# Vapeix_mini_Shield.net
KiCad netlist of a schematic drawn in Altium Designer
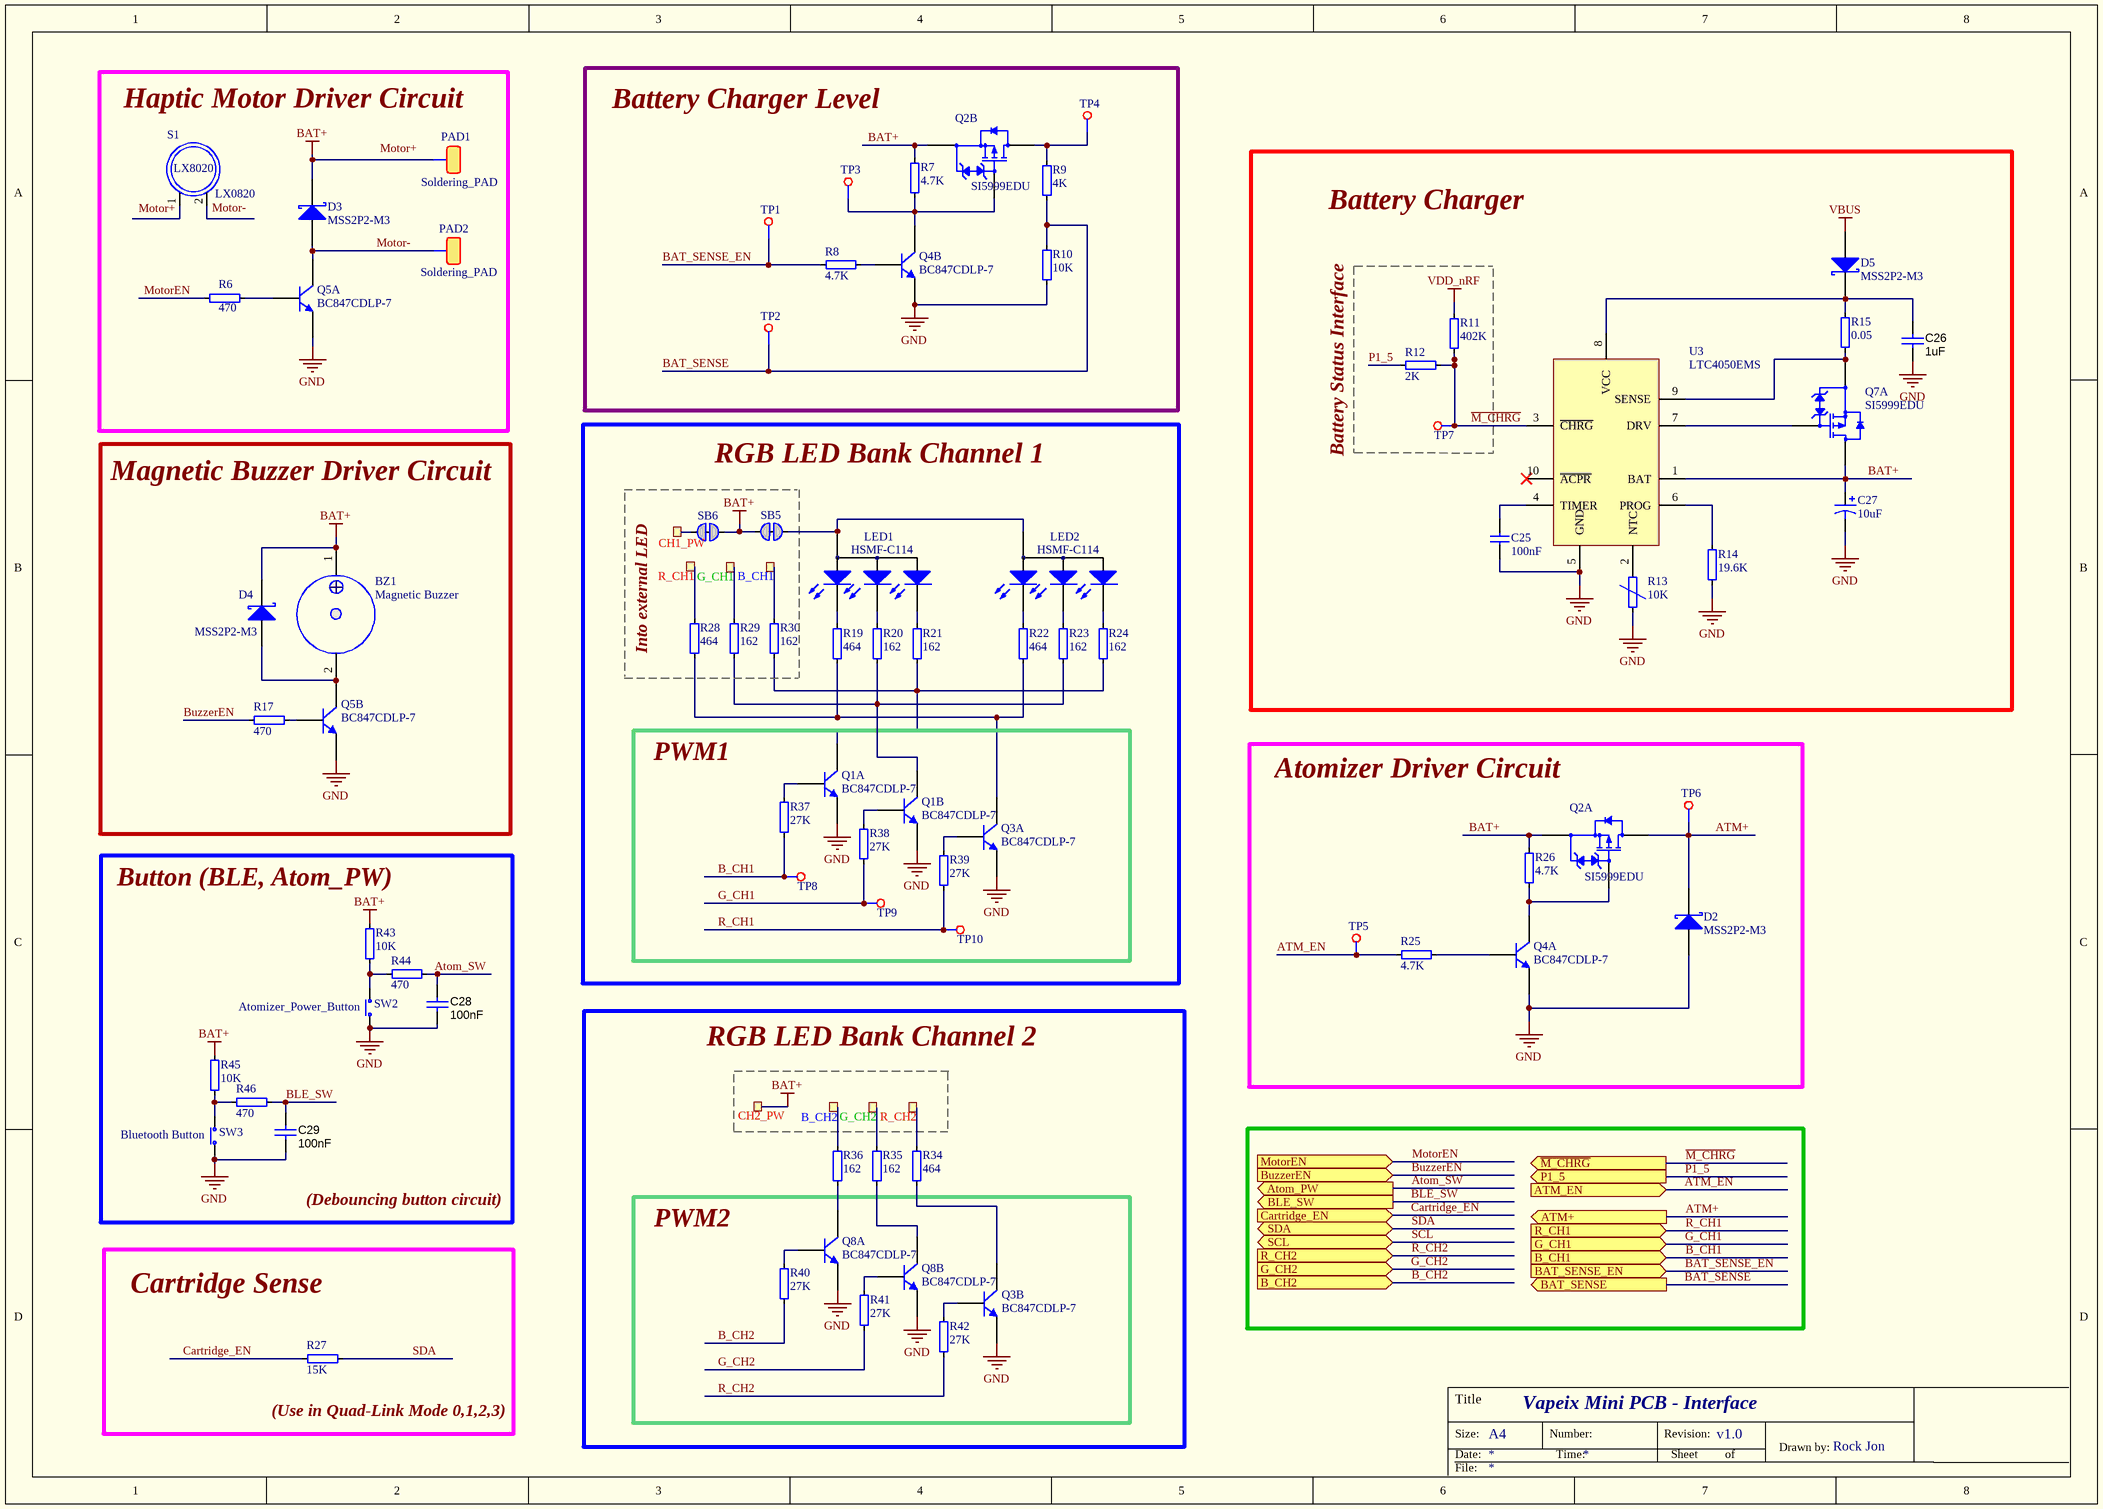
[diagram p0: Vapeix_mini_Shield.SchDoc]

(export (version "E")
  (design (tool "Eeschema 10.0.6"))
  (components
    (comp (ref "BZ1")
      (value "Magnetic Buzzer")
      (footprint "Magnetic Buzzer")
      (libsource (lib "VapeixS_LIB") (part "Magnetic Buzzer"))
    )
    (comp (ref "B_CH1")
      (value "TP")
      (footprint "TESTPAD-TH")
      (description "Testpoint, through hole")
      (fields (field (name "PART NUMBER") "Testpoint TH") (field (name "PUBLISHER") "Nordic Semiconductor"))
      (libsource (lib "pca10040") (part "TESTPAD_TH"))
    )
    (comp (ref "B_CH2")
      (value "TP")
      (footprint "TESTPAD-TH")
      (description "Testpoint, through hole")
      (fields (field (name "PART NUMBER") "Testpoint TH") (field (name "PUBLISHER") "Nordic Semiconductor"))
      (libsource (lib "pca10040") (part "TESTPAD_TH"))
    )
    (comp (ref "C25")
      (value "100nF")
      (footprint "C0201")
      (description "Capacitor, X7R, ±10%")
      (fields (field (name "PART NUMBER") "C0402-100n") (field (name "PUBLISHER") "Nordic Semiconductor"))
      (libsource (lib "Nordic Passive DB") (part "CAP"))
    )
    (comp (ref "C26")
      (value "~")
      (footprint "C0201")
      (description "CAP, CERM, 10 µF, 10 V, +/- 10%, X5R, 0805")
      (fields
        (field (name "PARTNUMBER") "GRM219R61A106KE44D")
        (field (name "VALUEDISPLAYED") "1uF")
        (field (name "MANUFACTURER") "MuRata")
        (field (name "PUBLISHER") "Texas Instruments")
      )
      (libsource (lib "Capacitor_Ceramic") (part "GRM219R61A106KE44D"))
    )
    (comp (ref "C27")
      (value "10uF")
      (footprint "CAPC1005X04L")
      (description "Polarized Capacitor (Surface Mount)")
      (fields (field (name "Comment") "Cap Pol3") (field (name "PUBLISHER") "Altium Limited"))
      (libsource (lib "Miscellaneous Devices") (part "Cap Pol3"))
    )
    (comp (ref "C28")
      (value "~")
      (footprint "C0201")
      (description "CAP, CERM, 10 µF, 10 V, +/- 10%, X5R, 0805")
      (fields
        (field (name "PARTNUMBER") "GRM219R61A106KE44D")
        (field (name "VALUEDISPLAYED") "100nF")
        (field (name "MANUFACTURER") "MuRata")
        (field (name "PUBLISHER") "Texas Instruments")
      )
      (libsource (lib "Capacitor_Ceramic") (part "GRM219R61A106KE44D"))
    )
    (comp (ref "C29")
      (value "~")
      (footprint "C0201")
      (description "CAP, CERM, 10 µF, 10 V, +/- 10%, X5R, 0805")
      (fields
        (field (name "PARTNUMBER") "GRM219R61A106KE44D")
        (field (name "VALUEDISPLAYED") "100nF")
        (field (name "MANUFACTURER") "MuRata")
        (field (name "PUBLISHER") "Texas Instruments")
      )
      (libsource (lib "Capacitor_Ceramic") (part "GRM219R61A106KE44D"))
    )
    (comp (ref "CH1_PW")
      (value "TP")
      (footprint "TESTPAD-TH")
      (description "Testpoint, through hole")
      (fields (field (name "PART NUMBER") "Testpoint TH") (field (name "PUBLISHER") "Nordic Semiconductor"))
      (libsource (lib "pca10040") (part "TESTPAD_TH"))
    )
    (comp (ref "CH2_PW")
      (value "TP")
      (footprint "TESTPAD-TH")
      (description "Testpoint, through hole")
      (fields (field (name "PART NUMBER") "Testpoint TH") (field (name "PUBLISHER") "Nordic Semiconductor"))
      (libsource (lib "pca10040") (part "TESTPAD_TH"))
    )
    (comp (ref "D2")
      (value "MSS2P2-M3")
      (footprint "MSS2P2-M3")
      (description "DIODE SCHOTTKY 20V 2A MICROSMP")
      (fields
        (field (name "MANUFACTURER") "Vishay Semiconductor Diodes Division")
        (field (name "MANUFACTURER PART NUMBER") "MSS2P2-M3/89A")
      )
      (libsource (lib "VapeixS_LIB") (part "MSS2P2-M3/89A"))
    )
    (comp (ref "D3")
      (value "MSS2P2-M3")
      (footprint "MSS2P2-M3")
      (description "DIODE SCHOTTKY 20V 2A MICROSMP")
      (fields
        (field (name "MANUFACTURER") "Vishay Semiconductor Diodes Division")
        (field (name "MANUFACTURER PART NUMBER") "MSS2P2-M3/89A")
      )
      (libsource (lib "VapeixS_LIB") (part "MSS2P2-M3/89A"))
    )
    (comp (ref "D4")
      (value "MSS2P2-M3")
      (footprint "MSS2P2-M3")
      (description "DIODE SCHOTTKY 20V 2A MICROSMP")
      (fields
        (field (name "MANUFACTURER") "Vishay Semiconductor Diodes Division")
        (field (name "MANUFACTURER PART NUMBER") "MSS2P2-M3/89A")
      )
      (libsource (lib "VapeixS_LIB") (part "MSS2P2-M3/89A"))
    )
    (comp (ref "D5")
      (value "MSS2P2-M3")
      (footprint "MSS2P2-M3")
      (description "DIODE SCHOTTKY 20V 2A MICROSMP")
      (fields
        (field (name "MANUFACTURER") "Vishay Semiconductor Diodes Division")
        (field (name "MANUFACTURER PART NUMBER") "MSS2P2-M3/89A")
      )
      (libsource (lib "VapeixS_LIB") (part "MSS2P2-M3/89A"))
    )
    (comp (ref "G_CH1")
      (value "TP")
      (footprint "TESTPAD-TH")
      (description "Testpoint, through hole")
      (fields (field (name "PART NUMBER") "Testpoint TH") (field (name "PUBLISHER") "Nordic Semiconductor"))
      (libsource (lib "pca10040") (part "TESTPAD_TH"))
    )
    (comp (ref "G_CH2")
      (value "TP")
      (footprint "TESTPAD-TH")
      (description "Testpoint, through hole")
      (fields (field (name "PART NUMBER") "Testpoint TH") (field (name "PUBLISHER") "Nordic Semiconductor"))
      (libsource (lib "pca10040") (part "TESTPAD_TH"))
    )
    (comp (ref "LED1")
      (value "HSMF-C114")
      (footprint "HSMF-C114")
      (description "LED RGB DIFFUSED 0606 SMD")
      (fields (field (name "MANUFACTURER") "Broadcom Limited"))
      (libsource (lib "VapeixS_LIB") (part "HSMF-C114"))
    )
    (comp (ref "LED2")
      (value "HSMF-C114")
      (footprint "HSMF-C114")
      (description "LED RGB DIFFUSED 0606 SMD")
      (fields (field (name "MANUFACTURER") "Broadcom Limited"))
      (libsource (lib "VapeixS_LIB") (part "HSMF-C114"))
    )
    (comp (ref "PAD1")
      (value "Soldering_PAD")
      (footprint "Soldering_PAD")
      (description "Soldering PAD")
      (libsource (lib "VapeixS_LIB") (part "Soldering_PAD"))
    )
    (comp (ref "PAD2")
      (value "Soldering_PAD")
      (footprint "Soldering_PAD")
      (description "Soldering PAD")
      (libsource (lib "VapeixS_LIB") (part "Soldering_PAD"))
    )
    (comp (ref "Q1")
      (value "BC847CDLP-7")
      (footprint "BC847CDLP-7")
      (description "TRANS 2NPN 45V 0.1A 6DFN")
      (fields (field (name "MANUFACTURER") "Diodes Incorporated"))
      (libsource (lib "") (part "BC847CDLP-7_1"))
    )
    (comp (ref "Q2")
      (value "SI5999EDU")
      (footprint "SI5999EDU")
      (description "MOSFET 2P-CH 20V 6A POWERPAK")
      (fields
        (field (name "MANUFACTURER") "Vishay Siliconix")
        (field (name "MANUFACTURER PART NUMBER") "SI5999EDU-T1-GE3")
      )
      (libsource (lib "") (part "SI5999EDU-T1-GE3_2"))
    )
    (comp (ref "Q3")
      (value "BC847CDLP-7")
      (footprint "BC847CDLP-7")
      (description "TRANS 2NPN 45V 0.1A 6DFN")
      (fields (field (name "MANUFACTURER") "Diodes Incorporated"))
      (libsource (lib "VapeixS_LIB") (part "BC847CDLP-7"))
    )
    (comp (ref "Q4")
      (value "BC847CDLP-7")
      (footprint "BC847CDLP-7")
      (description "TRANS 2NPN 45V 0.1A 6DFN")
      (fields (field (name "MANUFACTURER") "Diodes Incorporated"))
      (libsource (lib "") (part "BC847CDLP-7_3"))
    )
    (comp (ref "Q5")
      (value "BC847CDLP-7")
      (footprint "BC847CDLP-7")
      (description "TRANS 2NPN 45V 0.1A 6DFN")
      (fields (field (name "MANUFACTURER") "Diodes Incorporated"))
      (libsource (lib "") (part "BC847CDLP-7_1"))
    )
    (comp (ref "Q7")
      (value "SI5999EDU")
      (footprint "SI5999EDU")
      (description "MOSFET 2P-CH 20V 6A POWERPAK")
      (fields
        (field (name "MANUFACTURER") "Vishay Siliconix")
        (field (name "MANUFACTURER PART NUMBER") "SI5999EDU-T1-GE3")
      )
      (libsource (lib "VapeixS_LIB") (part "SI5999EDU-T1-GE3"))
    )
    (comp (ref "Q8")
      (value "BC847CDLP-7")
      (footprint "BC847CDLP-7")
      (description "TRANS 2NPN 45V 0.1A 6DFN")
      (fields (field (name "MANUFACTURER") "Diodes Incorporated"))
      (libsource (lib "VapeixS_LIB") (part "BC847CDLP-7"))
    )
    (comp (ref "R6")
      (value "470")
      (footprint "R0201")
      (description "Resistor, ±1%, 0.063W")
      (fields (field (name "PART NUMBER") "R0402-10k") (field (name "PUBLISHER") "Nordic Semiconductor"))
      (libsource (lib "Nordic Passive DB") (part "RES_1"))
    )
    (comp (ref "R7")
      (value "4.7K")
      (footprint "R0201")
      (description "Resistor, ±1%, 0.063W")
      (fields (field (name "PART NUMBER") "R0402-10k") (field (name "PUBLISHER") "Nordic Semiconductor"))
      (libsource (lib "Nordic Passive DB") (part "RES_1"))
    )
    (comp (ref "R8")
      (value "4.7K")
      (footprint "R0201")
      (description "Resistor, ±1%, 0.063W")
      (fields (field (name "PART NUMBER") "R0402-10k") (field (name "PUBLISHER") "Nordic Semiconductor"))
      (libsource (lib "Nordic Passive DB") (part "RES_1"))
    )
    (comp (ref "R9")
      (value "4K")
      (footprint "R0201")
      (description "Resistor, ±1%, 0.063W")
      (fields (field (name "PART NUMBER") "R0402-10k") (field (name "PUBLISHER") "Nordic Semiconductor"))
      (libsource (lib "Nordic Passive DB") (part "RES_1"))
    )
    (comp (ref "R10")
      (value "10K")
      (footprint "R0201")
      (description "Resistor, ±1%, 0.063W")
      (fields (field (name "PART NUMBER") "R0402-10k") (field (name "PUBLISHER") "Nordic Semiconductor"))
      (libsource (lib "Nordic Passive DB") (part "RES_1"))
    )
    (comp (ref "R11")
      (value "402K")
      (footprint "R0201")
      (description "Resistor, ±1%, 0.063W")
      (fields (field (name "PART NUMBER") "R0402-10k") (field (name "PUBLISHER") "Nordic Semiconductor"))
      (libsource (lib "Nordic Passive DB") (part "RES_1"))
    )
    (comp (ref "R12")
      (value "2K")
      (footprint "R0201")
      (description "Resistor, ±1%, 0.063W")
      (fields (field (name "PART NUMBER") "R0402-10k") (field (name "PUBLISHER") "Nordic Semiconductor"))
      (libsource (lib "Nordic Passive DB") (part "RES_1"))
    )
    (comp (ref "R13")
      (value "10K")
      (footprint "RL0503-5820-97-MS")
      (description "THERMISTOR MINI-SENS NTC 10K OHM")
      (fields
        (field (name "MANUFACTURER") "Amphenol Advanced Sensors")
        (field (name "MANUFACTURER PART NUMBER") "RL0503-5820-97-MS")
      )
      (libsource (lib "VapeixS_LIB") (part "RL0503-5820-97-MS"))
    )
    (comp (ref "R14")
      (value "19.6K")
      (footprint "R0201")
      (description "Resistor, ±1%, 0.063W")
      (fields (field (name "PART NUMBER") "R0402-10k") (field (name "PUBLISHER") "Nordic Semiconductor"))
      (libsource (lib "Nordic Passive DB") (part "RES_1"))
    )
    (comp (ref "R15")
      (value "0.05")
      (footprint "R0402")
      (description "Resistor, ±1%, 0.063W")
      (fields (field (name "PART NUMBER") "R0402-10k") (field (name "PUBLISHER") "Nordic Semiconductor"))
      (libsource (lib "Nordic Passive DB") (part "RES_1"))
    )
    (comp (ref "R17")
      (value "470")
      (footprint "RESC1005X04L")
      (description "Resistor, ±1%, 0.063W")
      (fields (field (name "PART NUMBER") "R0402-10k") (field (name "PUBLISHER") "Nordic Semiconductor"))
      (libsource (lib "Nordic Passive DB") (part "RES_1"))
    )
    (comp (ref "R19")
      (value "464")
      (footprint "R0201")
      (description "Resistor, ±1%, 0.063W")
      (fields (field (name "PART NUMBER") "R0402-10k") (field (name "PUBLISHER") "Nordic Semiconductor"))
      (libsource (lib "Nordic Passive DB") (part "RES_1"))
    )
    (comp (ref "R20")
      (value "162")
      (footprint "R0201")
      (description "Resistor, ±1%, 0.063W")
      (fields (field (name "PART NUMBER") "R0402-10k") (field (name "PUBLISHER") "Nordic Semiconductor"))
      (libsource (lib "Nordic Passive DB") (part "RES_1"))
    )
    (comp (ref "R21")
      (value "162")
      (footprint "R0201")
      (description "Resistor, ±1%, 0.063W")
      (fields (field (name "PART NUMBER") "R0402-10k") (field (name "PUBLISHER") "Nordic Semiconductor"))
      (libsource (lib "Nordic Passive DB") (part "RES_1"))
    )
    (comp (ref "R22")
      (value "464")
      (footprint "R0201")
      (description "Resistor, ±1%, 0.063W")
      (fields (field (name "PART NUMBER") "R0402-10k") (field (name "PUBLISHER") "Nordic Semiconductor"))
      (libsource (lib "Nordic Passive DB") (part "RES_1"))
    )
    (comp (ref "R23")
      (value "162")
      (footprint "R0201")
      (description "Resistor, ±1%, 0.063W")
      (fields (field (name "PART NUMBER") "R0402-10k") (field (name "PUBLISHER") "Nordic Semiconductor"))
      (libsource (lib "Nordic Passive DB") (part "RES_1"))
    )
    (comp (ref "R24")
      (value "162")
      (footprint "R0201")
      (description "Resistor, ±1%, 0.063W")
      (fields (field (name "PART NUMBER") "R0402-10k") (field (name "PUBLISHER") "Nordic Semiconductor"))
      (libsource (lib "Nordic Passive DB") (part "RES_1"))
    )
    (comp (ref "R25")
      (value "4.7K")
      (footprint "R0201")
      (description "Resistor, ±1%, 0.063W")
      (fields (field (name "PART NUMBER") "R0402-10k") (field (name "PUBLISHER") "Nordic Semiconductor"))
      (libsource (lib "Nordic Passive DB") (part "RES_1"))
    )
    (comp (ref "R26")
      (value "4.7K")
      (footprint "R0201")
      (description "Resistor, ±1%, 0.063W")
      (fields (field (name "PART NUMBER") "R0402-10k") (field (name "PUBLISHER") "Nordic Semiconductor"))
      (libsource (lib "Nordic Passive DB") (part "RES_1"))
    )
    (comp (ref "R27")
      (value "15K")
      (footprint "R0201")
      (description "Resistor, ±1%, 0.063W")
      (fields (field (name "PART NUMBER") "R0402-10k") (field (name "PUBLISHER") "Nordic Semiconductor"))
      (libsource (lib "Nordic Passive DB") (part "RES_1"))
    )
    (comp (ref "R28")
      (value "464")
      (footprint "R0201")
      (description "Resistor, ±1%, 0.063W")
      (fields (field (name "PART NUMBER") "R0402-10k") (field (name "PUBLISHER") "Nordic Semiconductor"))
      (libsource (lib "Nordic Passive DB") (part "RES_1"))
    )
    (comp (ref "R29")
      (value "162")
      (footprint "R0201")
      (description "Resistor, ±1%, 0.063W")
      (fields (field (name "PART NUMBER") "R0402-10k") (field (name "PUBLISHER") "Nordic Semiconductor"))
      (libsource (lib "Nordic Passive DB") (part "RES_1"))
    )
    (comp (ref "R30")
      (value "162")
      (footprint "R0201")
      (description "Resistor, ±1%, 0.063W")
      (fields (field (name "PART NUMBER") "R0402-10k") (field (name "PUBLISHER") "Nordic Semiconductor"))
      (libsource (lib "Nordic Passive DB") (part "RES_1"))
    )
    (comp (ref "R34")
      (value "464")
      (footprint "R0201")
      (description "Resistor, ±1%, 0.063W")
      (fields (field (name "PART NUMBER") "R0402-10k") (field (name "PUBLISHER") "Nordic Semiconductor"))
      (libsource (lib "Nordic Passive DB") (part "RES_1"))
    )
    (comp (ref "R35")
      (value "162")
      (footprint "R0201")
      (description "Resistor, ±1%, 0.063W")
      (fields (field (name "PART NUMBER") "R0402-10k") (field (name "PUBLISHER") "Nordic Semiconductor"))
      (libsource (lib "Nordic Passive DB") (part "RES_1"))
    )
    (comp (ref "R36")
      (value "162")
      (footprint "R0201")
      (description "Resistor, ±1%, 0.063W")
      (fields (field (name "PART NUMBER") "R0402-10k") (field (name "PUBLISHER") "Nordic Semiconductor"))
      (libsource (lib "Nordic Passive DB") (part "RES_1"))
    )
    (comp (ref "R37")
      (value "27K")
      (footprint "R0201")
      (description "Resistor, ±1%, 0.063W")
      (fields (field (name "PART NUMBER") "R0402-10k") (field (name "PUBLISHER") "Nordic Semiconductor"))
      (libsource (lib "Nordic Passive DB") (part "RES_1"))
    )
    (comp (ref "R38")
      (value "27K")
      (footprint "R0201")
      (description "Resistor, ±1%, 0.063W")
      (fields (field (name "PART NUMBER") "R0402-10k") (field (name "PUBLISHER") "Nordic Semiconductor"))
      (libsource (lib "Nordic Passive DB") (part "RES_1"))
    )
    (comp (ref "R39")
      (value "27K")
      (footprint "R0201")
      (description "Resistor, ±1%, 0.063W")
      (fields (field (name "PART NUMBER") "R0402-10k") (field (name "PUBLISHER") "Nordic Semiconductor"))
      (libsource (lib "Nordic Passive DB") (part "RES_1"))
    )
    (comp (ref "R40")
      (value "27K")
      (footprint "R0201")
      (description "Resistor, ±1%, 0.063W")
      (fields (field (name "PART NUMBER") "R0402-10k") (field (name "PUBLISHER") "Nordic Semiconductor"))
      (libsource (lib "Nordic Passive DB") (part "RES_1"))
    )
    (comp (ref "R41")
      (value "27K")
      (footprint "R0201")
      (description "Resistor, ±1%, 0.063W")
      (fields (field (name "PART NUMBER") "R0402-10k") (field (name "PUBLISHER") "Nordic Semiconductor"))
      (libsource (lib "Nordic Passive DB") (part "RES_1"))
    )
    (comp (ref "R42")
      (value "27K")
      (footprint "R0201")
      (description "Resistor, ±1%, 0.063W")
      (fields (field (name "PART NUMBER") "R0402-10k") (field (name "PUBLISHER") "Nordic Semiconductor"))
      (libsource (lib "Nordic Passive DB") (part "RES_1"))
    )
    (comp (ref "R43")
      (value "10K")
      (footprint "R0201")
      (description "Resistor, ±1%, 0.063W")
      (fields (field (name "PART NUMBER") "R0402-10k") (field (name "PUBLISHER") "Nordic Semiconductor"))
      (libsource (lib "Nordic Passive DB") (part "RES_1"))
    )
    (comp (ref "R44")
      (value "470")
      (footprint "R0201")
      (description "Resistor, ±1%, 0.063W")
      (fields (field (name "PART NUMBER") "R0402-10k") (field (name "PUBLISHER") "Nordic Semiconductor"))
      (libsource (lib "Nordic Passive DB") (part "RES_1"))
    )
    (comp (ref "R45")
      (value "10K")
      (footprint "R0201")
      (description "Resistor, ±1%, 0.063W")
      (fields (field (name "PART NUMBER") "R0402-10k") (field (name "PUBLISHER") "Nordic Semiconductor"))
      (libsource (lib "Nordic Passive DB") (part "RES_1"))
    )
    (comp (ref "R46")
      (value "470")
      (footprint "R0201")
      (description "Resistor, ±1%, 0.063W")
      (fields (field (name "PART NUMBER") "R0402-10k") (field (name "PUBLISHER") "Nordic Semiconductor"))
      (libsource (lib "Nordic Passive DB") (part "RES_1"))
    )
    (comp (ref "R_CH1")
      (value "TP")
      (footprint "TESTPAD-TH")
      (description "Testpoint, through hole")
      (fields (field (name "PART NUMBER") "Testpoint TH") (field (name "PUBLISHER") "Nordic Semiconductor"))
      (libsource (lib "pca10040") (part "TESTPAD_TH"))
    )
    (comp (ref "R_CH2")
      (value "TP")
      (footprint "TESTPAD-TH")
      (description "Testpoint, through hole")
      (fields (field (name "PART NUMBER") "Testpoint TH") (field (name "PUBLISHER") "Nordic Semiconductor"))
      (libsource (lib "pca10040") (part "TESTPAD_TH"))
    )
    (comp (ref "S1")
      (value "LX0820")
      (footprint "LX0820L20140926-01")
      (description "Coin Vibration Motor")
      (libsource (lib "VapeixS_LIB") (part "LX0820"))
    )
    (comp (ref "SB5")
      (value "Solderbridge")
      (footprint "Solderbridge_Shorted")
      (description "Shorted Solderbridge")
      (fields
        (field (name "PART NUMBER") "Solderbridge Shorted")
        (field (name "PUBLISHER") "Nordic Semiconductor")
      )
      (libsource (lib "Nordic Passive DB") (part "SOLDERBRIDGE_SHORTED"))
    )
    (comp (ref "SB6")
      (value "Solderbridge")
      (footprint "Solderbridge_Shorted")
      (description "Shorted Solderbridge")
      (fields
        (field (name "PART NUMBER") "Solderbridge Shorted")
        (field (name "PUBLISHER") "Nordic Semiconductor")
      )
      (libsource (lib "Nordic Passive DB") (part "SOLDERBRIDGE_SHORTED"))
    )
    (comp (ref "SW2")
      (value "Atomizer_Power_Button")
      (footprint "ALPS_SKHUxxx010_WO_GND")
      (description "ALPS - SKHUALE010 - Tactile Switch, SPNO, SMD, 6.5x6.2x2.5mm")
      (fields
        (field (name "PART NUMBER") "ALPS_SKHUALE010")
        (field (name "MANUFACTURER") "Alps")
        (field (name "PUBLISHER") "Nordic Semiconductor")
      )
      (libsource (lib "Nordic Discrete DB") (part "SW-PB"))
    )
    (comp (ref "SW3")
      (value "Bluetooth Button")
      (footprint "ALPS_SKHUxxx010_WO_GND")
      (description "ALPS - SKHUALE010 - Tactile Switch, SPNO, SMD, 6.5x6.2x2.5mm")
      (fields
        (field (name "PART NUMBER") "ALPS_SKHUALE010")
        (field (name "MANUFACTURER") "Alps")
        (field (name "PUBLISHER") "Nordic Semiconductor")
      )
      (libsource (lib "Nordic Discrete DB") (part "SW-PB"))
    )
    (comp (ref "TP1")
      (value "TP")
      (footprint "TP")
      (description "TEST POINT")
      (libsource (lib "VapeixS_LIB") (part "TP"))
    )
    (comp (ref "TP2")
      (value "TP")
      (footprint "TP")
      (description "TEST POINT")
      (libsource (lib "VapeixS_LIB") (part "TP"))
    )
    (comp (ref "TP3")
      (value "TP")
      (footprint "TP")
      (description "TEST POINT")
      (libsource (lib "VapeixS_LIB") (part "TP"))
    )
    (comp (ref "TP4")
      (value "TP")
      (footprint "TP")
      (description "TEST POINT")
      (libsource (lib "VapeixS_LIB") (part "TP"))
    )
    (comp (ref "TP5")
      (value "TP")
      (footprint "TP")
      (description "TEST POINT")
      (libsource (lib "") (part "TP_2"))
    )
    (comp (ref "TP6")
      (value "TP")
      (footprint "TP")
      (description "TEST POINT")
      (libsource (lib "") (part "TP_2"))
    )
    (comp (ref "TP7")
      (value "TP")
      (footprint "TP")
      (description "TEST POINT")
      (libsource (lib "") (part "TP_3"))
    )
    (comp (ref "TP8")
      (value "TP")
      (footprint "TP")
      (description "TEST POINT")
      (libsource (lib "") (part "TP_1"))
    )
    (comp (ref "TP9")
      (value "TP")
      (footprint "TP")
      (description "TEST POINT")
      (libsource (lib "") (part "TP_1"))
    )
    (comp (ref "TP10")
      (value "TP")
      (footprint "TP")
      (description "TEST POINT")
      (libsource (lib "") (part "TP_1"))
    )
    (comp (ref "U3")
      (value "LTC4050EMS")
      (footprint "LTC4050EMS")
      (description "IC BATT CHRG CNTRL LI-ION 10MSOP")
      (fields
        (field (name "MANUFACTURER") "Linear Technology")
        (field (name "MANUFACTURER PART NUMBER") "LTC4050EMS-4.1#PBF")
      )
      (libsource (lib "VapeixS_LIB") (part "LTC4050EMS-4.1#PBF"))
    )
  )
  (nets
    (net (code "4") (name "/ATM+") (class "Default")
      (node (ref "D2") (pin "2") (pinfunction "K_2") (pintype "passive"))
      (node (ref "Q2") (pin "7") (pinfunction "D1_7") (pintype "passive"))
      (node (ref "TP6") (pin "1") (pinfunction "TP_1") (pintype "passive"))
    )
    (net (code "5") (name "/ATM_EN") (class "Default")
      (node (ref "R25") (pin "1") (pinfunction "1_1") (pintype "passive"))
      (node (ref "TP5") (pin "1") (pinfunction "TP_1") (pintype "passive"))
    )
    (net (code "6") (name "/Atom_SW") (class "Default")
      (node (ref "C28") (pin "1") (pinfunction "1_1") (pintype "passive"))
      (node (ref "R44") (pin "1") (pinfunction "1_1") (pintype "passive"))
    )
    (net (code "8") (name "/BAT_SENSE") (class "Default")
      (node (ref "R10") (pin "1") (pinfunction "1_1") (pintype "passive"))
      (node (ref "R9") (pin "2") (pinfunction "2_2") (pintype "passive"))
      (node (ref "TP2") (pin "1") (pinfunction "TP_1") (pintype "passive"))
    )
    (net (code "9") (name "/BAT_SENSE_EN") (class "Default")
      (node (ref "R8") (pin "2") (pinfunction "2_2") (pintype "passive"))
      (node (ref "TP1") (pin "1") (pinfunction "TP_1") (pintype "passive"))
    )
    (net (code "10") (name "/BLE_SW") (class "Default")
      (node (ref "C29") (pin "1") (pinfunction "1_1") (pintype "passive"))
      (node (ref "R46") (pin "1") (pinfunction "1_1") (pintype "passive"))
    )
    (net (code "11") (name "/B_CH1") (class "Default")
      (node (ref "R37") (pin "2") (pinfunction "2_2") (pintype "passive"))
      (node (ref "TP8") (pin "1") (pinfunction "TP_1") (pintype "passive"))
    )
    (net (code "12") (name "/B_CH2") (class "Default")
      (node (ref "R40") (pin "2") (pinfunction "2_2") (pintype "passive"))
    )
    (net (code "17") (name "/BuzzerEN") (class "Default")
      (node (ref "R17") (pin "2") (pinfunction "2_2") (pintype "passive"))
    )
    (net (code "19") (name "/Cartridge_EN") (class "Default")
      (node (ref "R27") (pin "2") (pinfunction "2_2") (pintype "passive"))
    )
    (net (code "20") (name "/G_CH1") (class "Default")
      (node (ref "R38") (pin "2") (pinfunction "2_2") (pintype "passive"))
      (node (ref "TP9") (pin "1") (pinfunction "TP_1") (pintype "passive"))
    )
    (net (code "21") (name "/G_CH2") (class "Default")
      (node (ref "R41") (pin "2") (pinfunction "2_2") (pintype "passive"))
    )
    (net (code "26") (name "/Motor-") (class "Default")
      (node (ref "D3") (pin "1") (pinfunction "A_1") (pintype "passive"))
      (node (ref "PAD2") (pin "1") (pinfunction "TP_1") (pintype "passive"))
      (node (ref "Q5") (pin "3") (pinfunction "C1_3") (pintype "passive"))
    )
    (net (code "27") (name "/MotorEN") (class "Default")
      (node (ref "R6") (pin "2") (pinfunction "2_2") (pintype "passive"))
    )
    (net (code "28") (name "/P1_5") (class "Default")
      (node (ref "R12") (pin "1") (pinfunction "1_1") (pintype "passive"))
    )
    (net (code "33") (name "/R_CH1") (class "Default")
      (node (ref "R39") (pin "2") (pinfunction "2_2") (pintype "passive"))
      (node (ref "TP10") (pin "1") (pinfunction "TP_1") (pintype "passive"))
    )
    (net (code "34") (name "/R_CH2") (class "Default")
      (node (ref "R42") (pin "1") (pinfunction "1_1") (pintype "passive"))
    )
    (net (code "36") (name "/SDA") (class "Default")
      (node (ref "R27") (pin "1") (pinfunction "1_1") (pintype "passive"))
    )
    (net (code "37") (name "/~{M_CHRG}") (class "Default")
      (node (ref "R11") (pin "2") (pinfunction "2_2") (pintype "passive"))
      (node (ref "R12") (pin "2") (pinfunction "2_2") (pintype "passive"))
      (node (ref "TP7") (pin "1") (pinfunction "TP_1") (pintype "passive"))
      (node (ref "U3") (pin "3") (pinfunction "~{CHRG}_3") (pintype "passive"))
    )
    (net (code "38") (name "BAT+") (class "Default")
      (node (ref "BZ1") (pin "1") (pinfunction "P_1") (pintype "passive"))
      (node (ref "C27") (pin "1") (pinfunction "1_1") (pintype "passive"))
      (node (ref "CH2_PW") (pin "1") (pinfunction "1_1") (pintype "passive"))
      (node (ref "D3") (pin "2") (pinfunction "K_2") (pintype "passive"))
      (node (ref "D4") (pin "2") (pinfunction "K_2") (pintype "passive"))
      (node (ref "PAD1") (pin "1") (pinfunction "TP_1") (pintype "passive"))
      (node (ref "Q2") (pin "1") (pinfunction "S1_1") (pintype "passive"))
      (node (ref "Q2") (pin "3") (pinfunction "S2_3") (pintype "passive"))
      (node (ref "Q7") (pin "7") (pinfunction "D1_7") (pintype "passive"))
      (node (ref "R26") (pin "2") (pinfunction "2_2") (pintype "passive"))
      (node (ref "R43") (pin "2") (pinfunction "2_2") (pintype "passive"))
      (node (ref "R45") (pin "2") (pinfunction "2_2") (pintype "passive"))
      (node (ref "R7") (pin "1") (pinfunction "1_1") (pintype "passive"))
      (node (ref "SB5") (pin "2") (pinfunction "1_2") (pintype "passive"))
      (node (ref "SB6") (pin "2") (pinfunction "1_2") (pintype "passive"))
      (node (ref "U3") (pin "1") (pinfunction "BAT_1") (pintype "passive"))
    )
    (net (code "39") (name "GND") (class "Default")
      (node (ref "C25") (pin "2") (pinfunction "2_2") (pintype "passive"))
      (node (ref "C26") (pin "2") (pinfunction "2_2") (pintype "passive"))
      (node (ref "C27") (pin "2") (pinfunction "2_2") (pintype "passive"))
      (node (ref "C28") (pin "2") (pinfunction "2_2") (pintype "passive"))
      (node (ref "C29") (pin "2") (pinfunction "2_2") (pintype "passive"))
      (node (ref "D2") (pin "1") (pinfunction "A_1") (pintype "passive"))
      (node (ref "Q1") (pin "1") (pinfunction "E1_1") (pintype "passive"))
      (node (ref "Q1") (pin "4") (pinfunction "E2_4") (pintype "passive"))
      (node (ref "Q3") (pin "1") (pinfunction "E1_1") (pintype "passive"))
      (node (ref "Q3") (pin "4") (pinfunction "E2_4") (pintype "passive"))
      (node (ref "Q4") (pin "1") (pinfunction "E1_1") (pintype "passive"))
      (node (ref "Q4") (pin "4") (pinfunction "E2_4") (pintype "passive"))
      (node (ref "Q5") (pin "1") (pinfunction "E1_1") (pintype "passive"))
      (node (ref "Q5") (pin "4") (pinfunction "E2_4") (pintype "passive"))
      (node (ref "Q8") (pin "1") (pinfunction "E1_1") (pintype "passive"))
      (node (ref "Q8") (pin "4") (pinfunction "E2_4") (pintype "passive"))
      (node (ref "R10") (pin "2") (pinfunction "2_2") (pintype "passive"))
      (node (ref "R13") (pin "2") (pinfunction "2_2") (pintype "passive"))
      (node (ref "R14") (pin "2") (pinfunction "2_2") (pintype "passive"))
      (node (ref "SW2") (pin "1") (pinfunction "N.O_1") (pintype "passive"))
      (node (ref "SW3") (pin "1") (pinfunction "N.O_1") (pintype "passive"))
      (node (ref "U3") (pin "5") (pinfunction "GND_5") (pintype "passive"))
    )
    (net (code "40") (name "Net-(BZ1-M)") (class "Default")
      (node (ref "BZ1") (pin "2") (pinfunction "M_2") (pintype "passive"))
      (node (ref "D4") (pin "1") (pinfunction "A_1") (pintype "passive"))
      (node (ref "Q5") (pin "6") (pinfunction "C2_6") (pintype "passive"))
    )
    (net (code "41") (name "Net-(B_CH1-Pad1)") (class "Default")
      (node (ref "B_CH1") (pin "1") (pinfunction "1_1") (pintype "passive"))
      (node (ref "R30") (pin "1") (pinfunction "1_1") (pintype "passive"))
    )
    (net (code "42") (name "Net-(B_CH2-Pad1)") (class "Default")
      (node (ref "B_CH2") (pin "1") (pinfunction "1_1") (pintype "passive"))
      (node (ref "R36") (pin "1") (pinfunction "1_1") (pintype "passive"))
    )
    (net (code "43") (name "Net-(D5-K)") (class "Default")
      (node (ref "C26") (pin "1") (pinfunction "1_1") (pintype "passive"))
      (node (ref "D5") (pin "2") (pinfunction "K_2") (pintype "passive"))
      (node (ref "R15") (pin "1") (pinfunction "1_1") (pintype "passive"))
      (node (ref "U3") (pin "8") (pinfunction "VCC_8") (pintype "passive"))
    )
    (net (code "44") (name "Net-(G_CH1-Pad1)") (class "Default")
      (node (ref "G_CH1") (pin "1") (pinfunction "1_1") (pintype "passive"))
      (node (ref "R29") (pin "1") (pinfunction "1_1") (pintype "passive"))
    )
    (net (code "45") (name "Net-(G_CH2-Pad1)") (class "Default")
      (node (ref "G_CH2") (pin "1") (pinfunction "1_1") (pintype "passive"))
      (node (ref "R35") (pin "1") (pinfunction "1_1") (pintype "passive"))
    )
    (net (code "46") (name "Net-(LED1-ANODE)") (class "Default")
      (node (ref "LED1") (pin "1") (pinfunction "ANODE_1") (pintype "passive"))
      (node (ref "LED2") (pin "1") (pinfunction "ANODE_1") (pintype "passive"))
      (node (ref "SB5") (pin "1") (pinfunction "0_1") (pintype "passive"))
    )
    (net (code "47") (name "Net-(LED1-BLUE)") (class "Default")
      (node (ref "LED1") (pin "4") (pinfunction "BLUE_4") (pintype "passive"))
      (node (ref "R21") (pin "1") (pinfunction "1_1") (pintype "passive"))
    )
    (net (code "48") (name "Net-(LED1-GREEN)") (class "Default")
      (node (ref "LED1") (pin "3") (pinfunction "GREEN_3") (pintype "passive"))
      (node (ref "R20") (pin "1") (pinfunction "1_1") (pintype "passive"))
    )
    (net (code "49") (name "Net-(LED1-RED)") (class "Default")
      (node (ref "LED1") (pin "2") (pinfunction "RED_2") (pintype "passive"))
      (node (ref "R19") (pin "1") (pinfunction "1_1") (pintype "passive"))
    )
    (net (code "50") (name "Net-(LED2-BLUE)") (class "Default")
      (node (ref "LED2") (pin "4") (pinfunction "BLUE_4") (pintype "passive"))
      (node (ref "R24") (pin "1") (pinfunction "1_1") (pintype "passive"))
    )
    (net (code "51") (name "Net-(LED2-GREEN)") (class "Default")
      (node (ref "LED2") (pin "3") (pinfunction "GREEN_3") (pintype "passive"))
      (node (ref "R23") (pin "1") (pinfunction "1_1") (pintype "passive"))
    )
    (net (code "52") (name "Net-(LED2-RED)") (class "Default")
      (node (ref "LED2") (pin "2") (pinfunction "RED_2") (pintype "passive"))
      (node (ref "R22") (pin "1") (pinfunction "1_1") (pintype "passive"))
    )
    (net (code "53") (name "Net-(Q1A-B1)") (class "Default")
      (node (ref "Q1") (pin "2") (pinfunction "B1_2") (pintype "passive"))
      (node (ref "R37") (pin "1") (pinfunction "1_1") (pintype "passive"))
    )
    (net (code "54") (name "Net-(Q1A-C1)") (class "Default")
      (node (ref "Q1") (pin "3") (pinfunction "C1_3") (pintype "passive"))
      (node (ref "R21") (pin "2") (pinfunction "2_2") (pintype "passive"))
      (node (ref "R24") (pin "2") (pinfunction "2_2") (pintype "passive"))
      (node (ref "R30") (pin "2") (pinfunction "2_2") (pintype "passive"))
    )
    (net (code "55") (name "Net-(Q1B-B2)") (class "Default")
      (node (ref "Q1") (pin "5") (pinfunction "B2_5") (pintype "passive"))
      (node (ref "R38") (pin "1") (pinfunction "1_1") (pintype "passive"))
    )
    (net (code "56") (name "Net-(Q1B-C2)") (class "Default")
      (node (ref "Q1") (pin "6") (pinfunction "C2_6") (pintype "passive"))
      (node (ref "R20") (pin "2") (pinfunction "2_2") (pintype "passive"))
      (node (ref "R23") (pin "2") (pinfunction "2_2") (pintype "passive"))
      (node (ref "R29") (pin "2") (pinfunction "2_2") (pintype "passive"))
    )
    (net (code "57") (name "Net-(Q2A-G1)") (class "Default")
      (node (ref "Q2") (pin "2") (pinfunction "G1_2") (pintype "passive"))
      (node (ref "Q4") (pin "3") (pinfunction "C1_3") (pintype "passive"))
      (node (ref "R26") (pin "1") (pinfunction "1_1") (pintype "passive"))
    )
    (net (code "58") (name "Net-(Q2B-D2)") (class "Default")
      (node (ref "Q2") (pin "5") (pinfunction "D2_5") (pintype "passive"))
      (node (ref "R9") (pin "1") (pinfunction "1_1") (pintype "passive"))
      (node (ref "TP4") (pin "1") (pinfunction "TP_1") (pintype "passive"))
    )
    (net (code "59") (name "Net-(Q2B-G2)") (class "Default")
      (node (ref "Q2") (pin "4") (pinfunction "G2_4") (pintype "passive"))
      (node (ref "Q4") (pin "6") (pinfunction "C2_6") (pintype "passive"))
      (node (ref "R7") (pin "2") (pinfunction "2_2") (pintype "passive"))
      (node (ref "TP3") (pin "1") (pinfunction "TP_1") (pintype "passive"))
    )
    (net (code "60") (name "Net-(Q3A-B1)") (class "Default")
      (node (ref "Q3") (pin "2") (pinfunction "B1_2") (pintype "passive"))
      (node (ref "R39") (pin "1") (pinfunction "1_1") (pintype "passive"))
    )
    (net (code "61") (name "Net-(Q3A-C1)") (class "Default")
      (node (ref "Q3") (pin "3") (pinfunction "C1_3") (pintype "passive"))
      (node (ref "R19") (pin "2") (pinfunction "2_2") (pintype "passive"))
      (node (ref "R22") (pin "2") (pinfunction "2_2") (pintype "passive"))
      (node (ref "R28") (pin "2") (pinfunction "2_2") (pintype "passive"))
    )
    (net (code "62") (name "Net-(Q3B-B2)") (class "Default")
      (node (ref "Q3") (pin "5") (pinfunction "B2_5") (pintype "passive"))
      (node (ref "R42") (pin "2") (pinfunction "2_2") (pintype "passive"))
    )
    (net (code "63") (name "Net-(Q3B-C2)") (class "Default")
      (node (ref "Q3") (pin "6") (pinfunction "C2_6") (pintype "passive"))
      (node (ref "R34") (pin "2") (pinfunction "2_2") (pintype "passive"))
    )
    (net (code "64") (name "Net-(Q4A-B1)") (class "Default")
      (node (ref "Q4") (pin "2") (pinfunction "B1_2") (pintype "passive"))
      (node (ref "R25") (pin "2") (pinfunction "2_2") (pintype "passive"))
    )
    (net (code "65") (name "Net-(Q4B-B2)") (class "Default")
      (node (ref "Q4") (pin "5") (pinfunction "B2_5") (pintype "passive"))
      (node (ref "R8") (pin "1") (pinfunction "1_1") (pintype "passive"))
    )
    (net (code "66") (name "Net-(Q5A-B1)") (class "Default")
      (node (ref "Q5") (pin "2") (pinfunction "B1_2") (pintype "passive"))
      (node (ref "R6") (pin "1") (pinfunction "1_1") (pintype "passive"))
    )
    (net (code "67") (name "Net-(Q5B-B2)") (class "Default")
      (node (ref "Q5") (pin "5") (pinfunction "B2_5") (pintype "passive"))
      (node (ref "R17") (pin "1") (pinfunction "1_1") (pintype "passive"))
    )
    (net (code "68") (name "Net-(Q7A-G1)") (class "Default")
      (node (ref "Q7") (pin "2") (pinfunction "G1_2") (pintype "passive"))
      (node (ref "U3") (pin "7") (pinfunction "DRV_7") (pintype "passive"))
    )
    (net (code "69") (name "Net-(Q7A-S1)") (class "Default")
      (node (ref "Q7") (pin "1") (pinfunction "S1_1") (pintype "passive"))
      (node (ref "R15") (pin "2") (pinfunction "2_2") (pintype "passive"))
      (node (ref "U3") (pin "9") (pinfunction "SENSE_9") (pintype "passive"))
    )
    (net (code "70") (name "Net-(Q8A-B1)") (class "Default")
      (node (ref "Q8") (pin "2") (pinfunction "B1_2") (pintype "passive"))
      (node (ref "R40") (pin "1") (pinfunction "1_1") (pintype "passive"))
    )
    (net (code "71") (name "Net-(Q8A-C1)") (class "Default")
      (node (ref "Q8") (pin "3") (pinfunction "C1_3") (pintype "passive"))
      (node (ref "R36") (pin "2") (pinfunction "2_2") (pintype "passive"))
    )
    (net (code "72") (name "Net-(Q8B-B2)") (class "Default")
      (node (ref "Q8") (pin "5") (pinfunction "B2_5") (pintype "passive"))
      (node (ref "R41") (pin "1") (pinfunction "1_1") (pintype "passive"))
    )
    (net (code "73") (name "Net-(Q8B-C2)") (class "Default")
      (node (ref "Q8") (pin "6") (pinfunction "C2_6") (pintype "passive"))
      (node (ref "R35") (pin "2") (pinfunction "2_2") (pintype "passive"))
    )
    (net (code "74") (name "Net-(R28-Pad1)") (class "Default")
      (node (ref "R28") (pin "1") (pinfunction "1_1") (pintype "passive"))
      (node (ref "R_CH1") (pin "1") (pinfunction "1_1") (pintype "passive"))
    )
    (net (code "75") (name "Net-(R34-Pad1)") (class "Default")
      (node (ref "R34") (pin "1") (pinfunction "1_1") (pintype "passive"))
      (node (ref "R_CH2") (pin "1") (pinfunction "1_1") (pintype "passive"))
    )
    (net (code "76") (name "Net-(SB6-0)") (class "Default")
      (node (ref "CH1_PW") (pin "1") (pinfunction "1_1") (pintype "passive"))
      (node (ref "SB6") (pin "1") (pinfunction "0_1") (pintype "passive"))
    )
    (net (code "77") (name "Net-(SW2-COM)") (class "Default")
      (node (ref "R43") (pin "1") (pinfunction "1_1") (pintype "passive"))
      (node (ref "R44") (pin "2") (pinfunction "2_2") (pintype "passive"))
      (node (ref "SW2") (pin "2") (pinfunction "COM_2") (pintype "passive"))
    )
    (net (code "78") (name "Net-(SW3-COM)") (class "Default")
      (node (ref "R45") (pin "1") (pinfunction "1_1") (pintype "passive"))
      (node (ref "R46") (pin "2") (pinfunction "2_2") (pintype "passive"))
      (node (ref "SW3") (pin "2") (pinfunction "COM_2") (pintype "passive"))
    )
    (net (code "79") (name "Net-(U3-NTC)") (class "Default")
      (node (ref "R13") (pin "1") (pinfunction "1_1") (pintype "passive"))
      (node (ref "U3") (pin "2") (pinfunction "NTC_2") (pintype "passive"))
    )
    (net (code "80") (name "Net-(U3-PROG)") (class "Default")
      (node (ref "R14") (pin "1") (pinfunction "1_1") (pintype "passive"))
      (node (ref "U3") (pin "6") (pinfunction "PROG_6") (pintype "passive"))
    )
    (net (code "81") (name "Net-(U3-TIMER)") (class "Default")
      (node (ref "C25") (pin "1") (pinfunction "1_1") (pintype "passive"))
      (node (ref "U3") (pin "4") (pinfunction "TIMER_4") (pintype "passive"))
    )
    (net (code "82") (name "VBUS") (class "Default")
      (node (ref "D5") (pin "1") (pinfunction "A_1") (pintype "passive"))
    )
    (net (code "83") (name "VDD_nRF") (class "Default")
      (node (ref "R11") (pin "1") (pinfunction "1_1") (pintype "passive"))
    )
    (net (code "84") (name "unconnected-(S1-GND-Pad2)") (class "Default")
      (node (ref "S1") (pin "2") (pinfunction "GND_2") (pintype "passive"))
    )
    (net (code "85") (name "unconnected-(S1-PW-Pad1)") (class "Default")
      (node (ref "S1") (pin "1") (pinfunction "PW_1") (pintype "passive"))
    )
    (net (code "86") (name "unconnected-(U3-~{ACPR}-Pad10)") (class "Default")
      (node (ref "U3") (pin "10") (pinfunction "~{ACPR}_10") (pintype "passive+no_connect"))
    )
  )
)
